# ChargePump.net
KiCad netlist of a schematic drawn in EAGLE
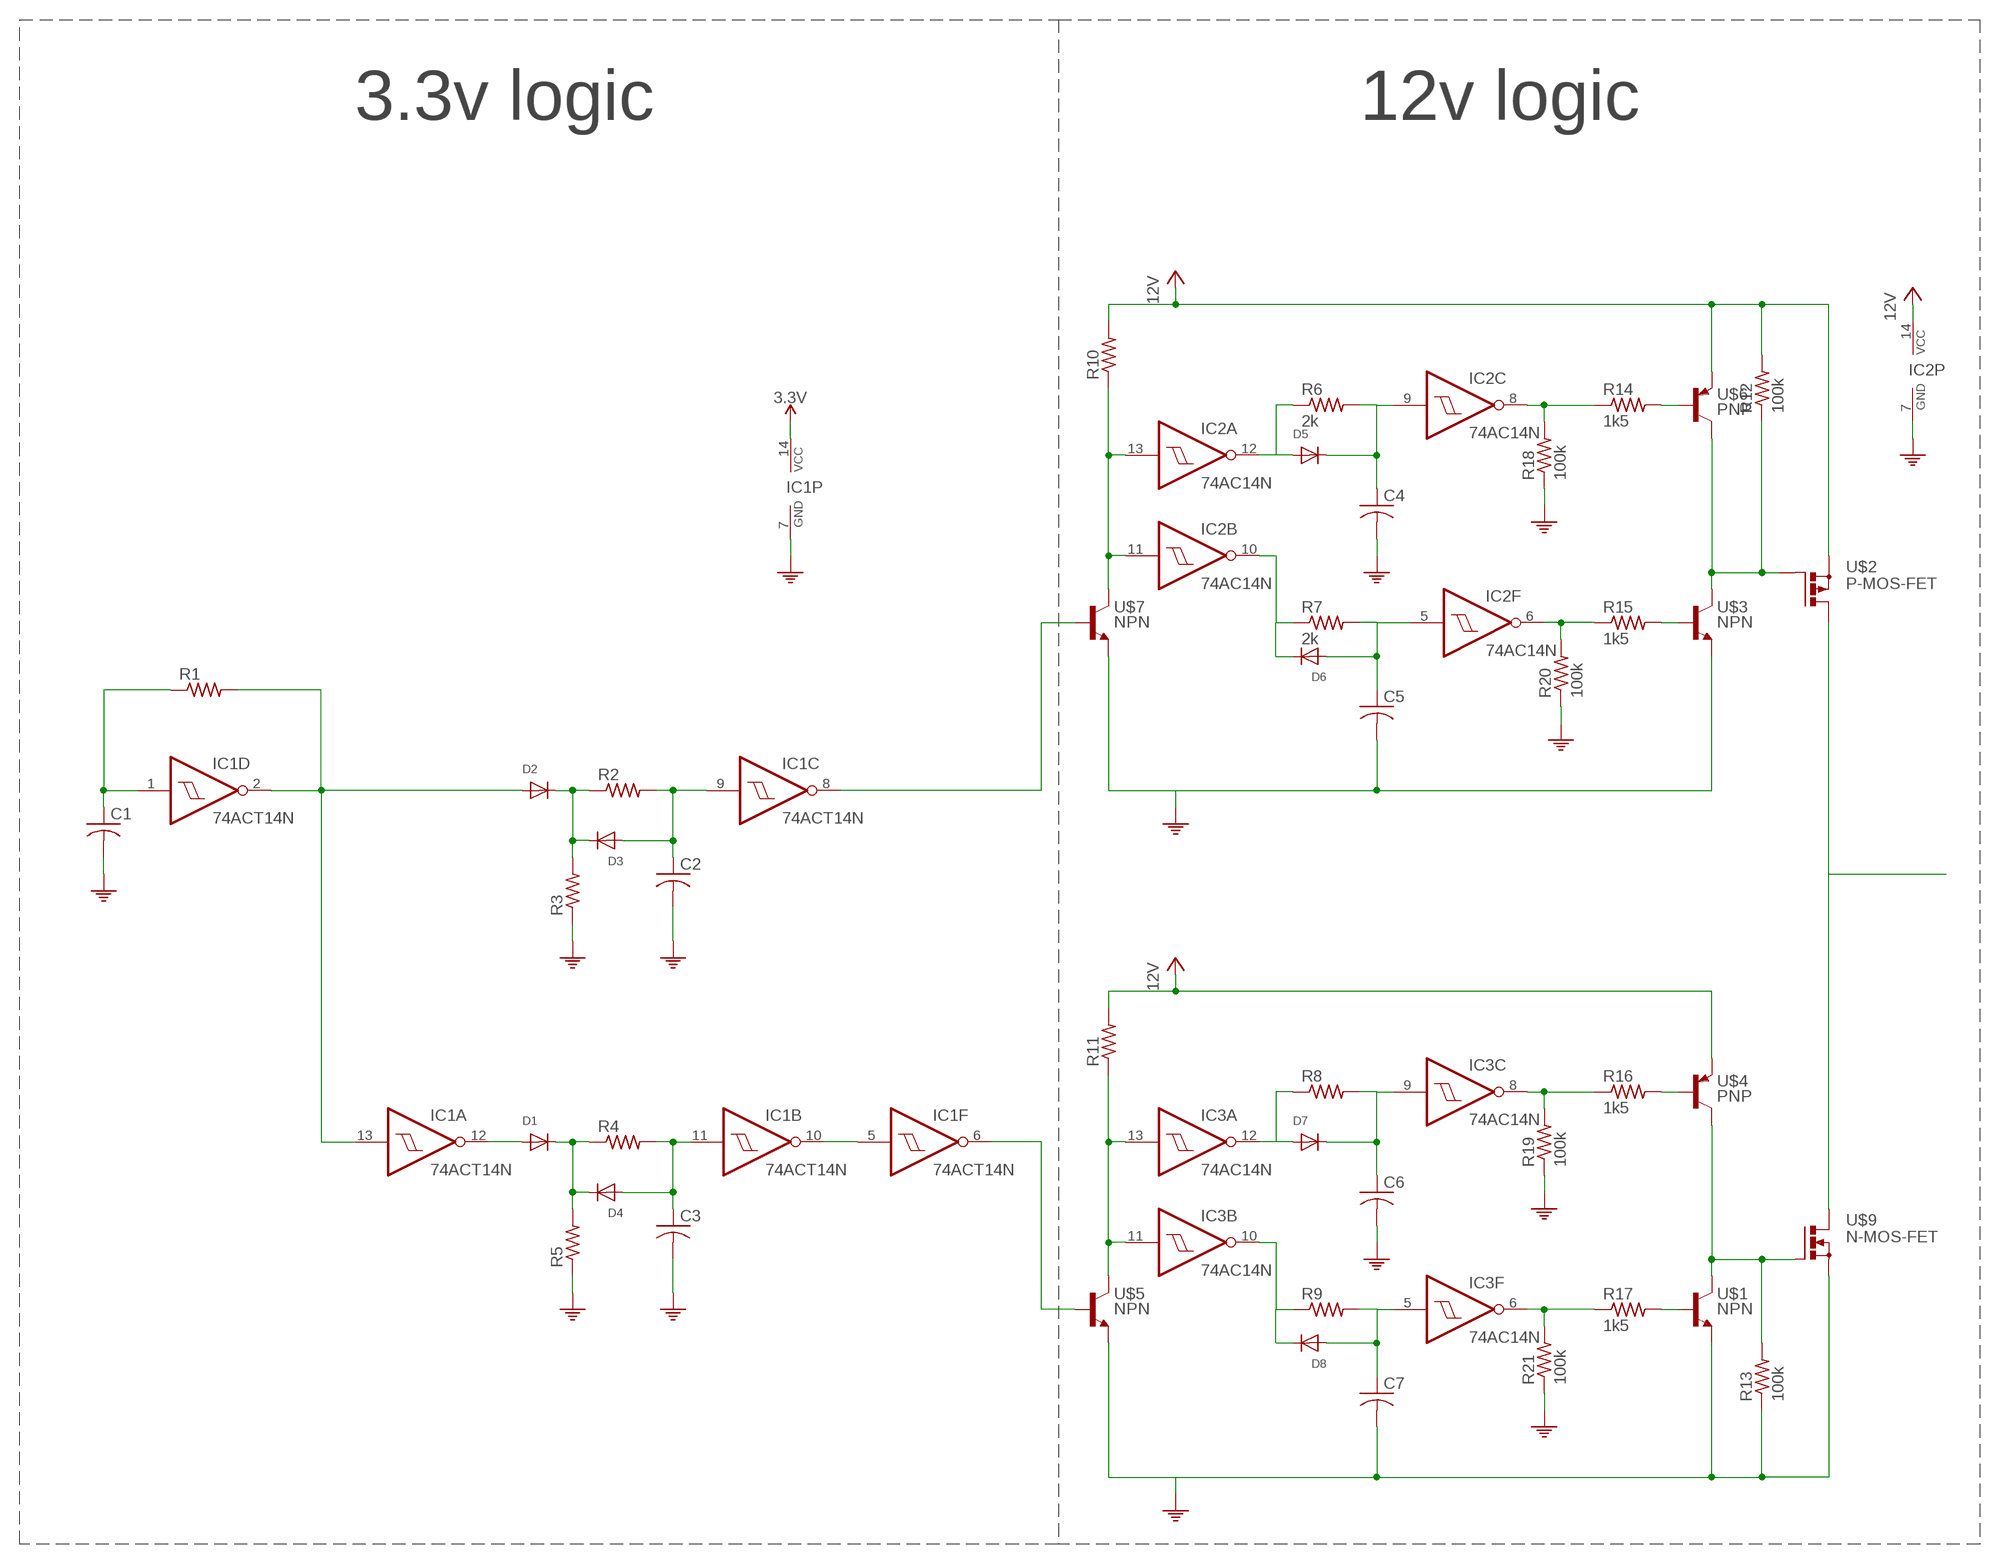
[diagram p0: schematic, sheet 1]

(export (version "E")
  (design (tool "Eeschema 10.0.6"))
  (components
    (comp (ref "C1")
      (value "C-USC0603")
      (footprint "eagle-import:C0603")
      (libsource (lib "eagle-import") (part "C-USC0603"))
    )
    (comp (ref "C2")
      (value "C-USC0603")
      (footprint "eagle-import:C0603")
      (libsource (lib "eagle-import") (part "C-USC0603"))
    )
    (comp (ref "C3")
      (value "C-USC0603")
      (footprint "eagle-import:C0603")
      (libsource (lib "eagle-import") (part "C-USC0603"))
    )
    (comp (ref "C4")
      (value "C-USC0603")
      (footprint "eagle-import:C0603")
      (libsource (lib "eagle-import") (part "C-USC0603"))
    )
    (comp (ref "C5")
      (value "C-USC0603")
      (footprint "eagle-import:C0603")
      (libsource (lib "eagle-import") (part "C-USC0603"))
    )
    (comp (ref "C6")
      (value "C-USC0603")
      (footprint "eagle-import:C0603")
      (libsource (lib "eagle-import") (part "C-USC0603"))
    )
    (comp (ref "C7")
      (value "C-USC0603")
      (footprint "eagle-import:C0603")
      (libsource (lib "eagle-import") (part "C-USC0603"))
    )
    (comp (ref "D1")
      (value "DIODEDO-1N4148")
      (footprint "eagle-import:DO-1N4148")
      (libsource (lib "eagle-import") (part "DIODEDO-1N4148"))
    )
    (comp (ref "D2")
      (value "DIODEDO-1N4148")
      (footprint "eagle-import:DO-1N4148")
      (libsource (lib "eagle-import") (part "DIODEDO-1N4148"))
    )
    (comp (ref "D3")
      (value "DIODEDO-1N4148")
      (footprint "eagle-import:DO-1N4148")
      (libsource (lib "eagle-import") (part "DIODEDO-1N4148"))
    )
    (comp (ref "D4")
      (value "DIODEDO-1N4148")
      (footprint "eagle-import:DO-1N4148")
      (libsource (lib "eagle-import") (part "DIODEDO-1N4148"))
    )
    (comp (ref "D5")
      (value "DIODEDO-1N4148")
      (footprint "eagle-import:DO-1N4148")
      (libsource (lib "eagle-import") (part "DIODEDO-1N4148"))
    )
    (comp (ref "D6")
      (value "DIODEDO-1N4148")
      (footprint "eagle-import:DO-1N4148")
      (libsource (lib "eagle-import") (part "DIODEDO-1N4148"))
    )
    (comp (ref "D7")
      (value "DIODEDO-1N4148")
      (footprint "eagle-import:DO-1N4148")
      (libsource (lib "eagle-import") (part "DIODEDO-1N4148"))
    )
    (comp (ref "D8")
      (value "DIODEDO-1N4148")
      (footprint "eagle-import:DO-1N4148")
      (libsource (lib "eagle-import") (part "DIODEDO-1N4148"))
    )
    (comp (ref "IC1")
      (value "74ACT14N")
      (footprint "eagle-import:DIL14")
      (libsource (lib "eagle-import") (part "7414NACT"))
    )
    (comp (ref "IC2")
      (value "74AC14N")
      (footprint "eagle-import:DIL14")
      (libsource (lib "eagle-import") (part "7414NAC"))
    )
    (comp (ref "IC3")
      (value "74AC14N")
      (footprint "eagle-import:DIL14")
      (libsource (lib "eagle-import") (part "7414NAC"))
    )
    (comp (ref "R1")
      (value "R-US_R0603")
      (footprint "eagle-import:R0603")
      (libsource (lib "eagle-import") (part "R-US_R0603"))
    )
    (comp (ref "R2")
      (value "R-US_R0603")
      (footprint "eagle-import:R0603")
      (libsource (lib "eagle-import") (part "R-US_R0603"))
    )
    (comp (ref "R3")
      (value "R-US_R0603")
      (footprint "eagle-import:R0603")
      (libsource (lib "eagle-import") (part "R-US_R0603"))
    )
    (comp (ref "R4")
      (value "R-US_R0603")
      (footprint "eagle-import:R0603")
      (libsource (lib "eagle-import") (part "R-US_R0603"))
    )
    (comp (ref "R5")
      (value "R-US_R0603")
      (footprint "eagle-import:R0603")
      (libsource (lib "eagle-import") (part "R-US_R0603"))
    )
    (comp (ref "R6")
      (value "2k")
      (footprint "eagle-import:R0603")
      (libsource (lib "eagle-import") (part "R-US_R0603"))
    )
    (comp (ref "R7")
      (value "2k")
      (footprint "eagle-import:R0603")
      (libsource (lib "eagle-import") (part "R-US_R0603"))
    )
    (comp (ref "R8")
      (value "R-US_R0603")
      (footprint "eagle-import:R0603")
      (libsource (lib "eagle-import") (part "R-US_R0603"))
    )
    (comp (ref "R9")
      (value "R-US_R0603")
      (footprint "eagle-import:R0603")
      (libsource (lib "eagle-import") (part "R-US_R0603"))
    )
    (comp (ref "R10")
      (value "R-US_R0603")
      (footprint "eagle-import:R0603")
      (libsource (lib "eagle-import") (part "R-US_R0603"))
    )
    (comp (ref "R11")
      (value "R-US_R0603")
      (footprint "eagle-import:R0603")
      (libsource (lib "eagle-import") (part "R-US_R0603"))
    )
    (comp (ref "R12")
      (value "100k")
      (footprint "eagle-import:R0603")
      (libsource (lib "eagle-import") (part "R-US_R0603"))
    )
    (comp (ref "R13")
      (value "100k")
      (footprint "eagle-import:R0603")
      (libsource (lib "eagle-import") (part "R-US_R0603"))
    )
    (comp (ref "R14")
      (value "1k5")
      (footprint "eagle-import:R0603")
      (libsource (lib "eagle-import") (part "R-US_R0603"))
    )
    (comp (ref "R15")
      (value "1k5")
      (footprint "eagle-import:R0603")
      (libsource (lib "eagle-import") (part "R-US_R0603"))
    )
    (comp (ref "R16")
      (value "1k5")
      (footprint "eagle-import:R0603")
      (libsource (lib "eagle-import") (part "R-US_R0603"))
    )
    (comp (ref "R17")
      (value "1k5")
      (footprint "eagle-import:R0603")
      (libsource (lib "eagle-import") (part "R-US_R0603"))
    )
    (comp (ref "R18")
      (value "100k")
      (footprint "eagle-import:R0603")
      (libsource (lib "eagle-import") (part "R-US_R0603"))
    )
    (comp (ref "R19")
      (value "100k")
      (footprint "eagle-import:R0603")
      (libsource (lib "eagle-import") (part "R-US_R0603"))
    )
    (comp (ref "R20")
      (value "100k")
      (footprint "eagle-import:R0603")
      (libsource (lib "eagle-import") (part "R-US_R0603"))
    )
    (comp (ref "R21")
      (value "100k")
      (footprint "eagle-import:R0603")
      (libsource (lib "eagle-import") (part "R-US_R0603"))
    )
    (comp (ref "U$1")
      (value "NPN")
      (footprint "eagle-import:SOT23")
      (libsource (lib "eagle-import") (part "NPN"))
    )
    (comp (ref "U$2")
      (value "P-MOS-FET")
      (footprint "eagle-import:SOT23")
      (libsource (lib "eagle-import") (part "P-MOS-FET"))
    )
    (comp (ref "U$3")
      (value "NPN")
      (footprint "eagle-import:SOT23")
      (libsource (lib "eagle-import") (part "NPN"))
    )
    (comp (ref "U$4")
      (value "PNP")
      (footprint "eagle-import:SOT23")
      (libsource (lib "eagle-import") (part "PNP"))
    )
    (comp (ref "U$5")
      (value "NPN")
      (footprint "eagle-import:SOT23")
      (libsource (lib "eagle-import") (part "NPN"))
    )
    (comp (ref "U$6")
      (value "PNP")
      (footprint "eagle-import:SOT23")
      (libsource (lib "eagle-import") (part "PNP"))
    )
    (comp (ref "U$7")
      (value "NPN")
      (footprint "eagle-import:SOT23")
      (libsource (lib "eagle-import") (part "NPN"))
    )
    (comp (ref "U$9")
      (value "N-MOS-FET")
      (footprint "eagle-import:SOT23")
      (libsource (lib "eagle-import") (part "N-MOS-FET"))
    )
  )
  (nets
    (net (code "1") (name "3.3V") (class "Default")
      (node (ref "IC1") (pin "14") (pinfunction "VCC_14") (pintype "power_in"))
    )
    (net (code "2") (name "12V") (class "Default")
      (node (ref "IC2") (pin "14") (pinfunction "VCC_14") (pintype "power_in"))
      (node (ref "R10") (pin "2") (pinfunction "2_2") (pintype "passive"))
      (node (ref "R11") (pin "2") (pinfunction "2_2") (pintype "passive"))
      (node (ref "R12") (pin "2") (pinfunction "2_2") (pintype "passive"))
      (node (ref "U$2") (pin "C") (pinfunction "S_C") (pintype "passive"))
      (node (ref "U$4") (pin "E") (pinfunction "E_E") (pintype "passive"))
      (node (ref "U$6") (pin "E") (pinfunction "E_E") (pintype "passive"))
    )
    (net (code "3") (name "GND") (class "Default")
      (node (ref "C1") (pin "2") (pinfunction "2_2") (pintype "passive"))
      (node (ref "C2") (pin "2") (pinfunction "2_2") (pintype "passive"))
      (node (ref "C3") (pin "2") (pinfunction "2_2") (pintype "passive"))
      (node (ref "C4") (pin "2") (pinfunction "2_2") (pintype "passive"))
      (node (ref "C5") (pin "2") (pinfunction "2_2") (pintype "passive"))
      (node (ref "C6") (pin "2") (pinfunction "2_2") (pintype "passive"))
      (node (ref "C7") (pin "2") (pinfunction "2_2") (pintype "passive"))
      (node (ref "IC1") (pin "7") (pinfunction "GND_7") (pintype "power_in"))
      (node (ref "IC2") (pin "7") (pinfunction "GND_7") (pintype "power_in"))
      (node (ref "R13") (pin "1") (pinfunction "1_1") (pintype "passive"))
      (node (ref "R18") (pin "1") (pinfunction "1_1") (pintype "passive"))
      (node (ref "R19") (pin "1") (pinfunction "1_1") (pintype "passive"))
      (node (ref "R20") (pin "1") (pinfunction "1_1") (pintype "passive"))
      (node (ref "R21") (pin "1") (pinfunction "1_1") (pintype "passive"))
      (node (ref "R3") (pin "1") (pinfunction "1_1") (pintype "passive"))
      (node (ref "R5") (pin "1") (pinfunction "1_1") (pintype "passive"))
      (node (ref "U$1") (pin "E") (pinfunction "E_E") (pintype "passive"))
      (node (ref "U$3") (pin "E") (pinfunction "E_E") (pintype "passive"))
      (node (ref "U$5") (pin "E") (pinfunction "E_E") (pintype "passive"))
      (node (ref "U$7") (pin "E") (pinfunction "E_E") (pintype "passive"))
      (node (ref "U$9") (pin "E") (pinfunction "S_E") (pintype "passive"))
    )
    (net (code "4") (name "Net-(D1-PadC)") (class "Default")
      (node (ref "D1") (pin "C") (pinfunction "C_C") (pintype "passive"))
      (node (ref "D4") (pin "C") (pinfunction "C_C") (pintype "passive"))
      (node (ref "R4") (pin "1") (pinfunction "1_1") (pintype "passive"))
      (node (ref "R5") (pin "2") (pinfunction "2_2") (pintype "passive"))
    )
    (net (code "5") (name "Net-(D2-PadC)") (class "Default")
      (node (ref "D2") (pin "C") (pinfunction "C_C") (pintype "passive"))
      (node (ref "D3") (pin "C") (pinfunction "C_C") (pintype "passive"))
      (node (ref "R2") (pin "1") (pinfunction "1_1") (pintype "passive"))
      (node (ref "R3") (pin "2") (pinfunction "2_2") (pintype "passive"))
    )
    (net (code "6") (name "Net-(IC1A-I)") (class "Default")
      (node (ref "D2") (pin "A") (pinfunction "A_A") (pintype "passive"))
      (node (ref "IC1") (pin "13") (pinfunction "I_13") (pintype "input"))
      (node (ref "IC1") (pin "2") (pinfunction "O_2") (pintype "output"))
      (node (ref "R1") (pin "2") (pinfunction "2_2") (pintype "passive"))
    )
    (net (code "7") (name "Net-(IC1A-O)") (class "Default")
      (node (ref "D1") (pin "A") (pinfunction "A_A") (pintype "passive"))
      (node (ref "IC1") (pin "12") (pinfunction "O_12") (pintype "output"))
    )
    (net (code "8") (name "Net-(IC1B-I)") (class "Default")
      (node (ref "C3") (pin "1") (pinfunction "1_1") (pintype "passive"))
      (node (ref "D4") (pin "A") (pinfunction "A_A") (pintype "passive"))
      (node (ref "IC1") (pin "11") (pinfunction "I_11") (pintype "input"))
      (node (ref "R4") (pin "2") (pinfunction "2_2") (pintype "passive"))
    )
    (net (code "9") (name "Net-(IC1B-O)") (class "Default")
      (node (ref "IC1") (pin "10") (pinfunction "O_10") (pintype "output"))
      (node (ref "IC1") (pin "5") (pinfunction "I_5") (pintype "input"))
    )
    (net (code "10") (name "Net-(IC1C-I)") (class "Default")
      (node (ref "C2") (pin "1") (pinfunction "1_1") (pintype "passive"))
      (node (ref "D3") (pin "A") (pinfunction "A_A") (pintype "passive"))
      (node (ref "IC1") (pin "9") (pinfunction "I_9") (pintype "input"))
      (node (ref "R2") (pin "2") (pinfunction "2_2") (pintype "passive"))
    )
    (net (code "11") (name "Net-(IC1C-O)") (class "Default")
      (node (ref "IC1") (pin "8") (pinfunction "O_8") (pintype "output"))
      (node (ref "U$7") (pin "B") (pinfunction "B_B") (pintype "passive"))
    )
    (net (code "12") (name "Net-(IC1D-I)") (class "Default")
      (node (ref "C1") (pin "1") (pinfunction "1_1") (pintype "passive"))
      (node (ref "IC1") (pin "1") (pinfunction "I_1") (pintype "input"))
      (node (ref "R1") (pin "1") (pinfunction "1_1") (pintype "passive"))
    )
    (net (code "13") (name "Net-(IC1F-O)") (class "Default")
      (node (ref "IC1") (pin "6") (pinfunction "O_6") (pintype "output"))
      (node (ref "U$5") (pin "B") (pinfunction "B_B") (pintype "passive"))
    )
    (net (code "14") (name "Net-(IC2A-I)") (class "Default")
      (node (ref "IC2") (pin "11") (pinfunction "I_11") (pintype "input"))
      (node (ref "IC2") (pin "13") (pinfunction "I_13") (pintype "input"))
      (node (ref "R10") (pin "1") (pinfunction "1_1") (pintype "passive"))
      (node (ref "U$7") (pin "C") (pinfunction "C_C") (pintype "passive"))
    )
    (net (code "15") (name "Net-(IC2A-O)") (class "Default")
      (node (ref "D5") (pin "A") (pinfunction "A_A") (pintype "passive"))
      (node (ref "IC2") (pin "12") (pinfunction "O_12") (pintype "output"))
      (node (ref "R6") (pin "1") (pinfunction "1_1") (pintype "passive"))
    )
    (net (code "16") (name "Net-(IC2B-O)") (class "Default")
      (node (ref "D6") (pin "C") (pinfunction "C_C") (pintype "passive"))
      (node (ref "IC2") (pin "10") (pinfunction "O_10") (pintype "output"))
      (node (ref "R7") (pin "1") (pinfunction "1_1") (pintype "passive"))
    )
    (net (code "17") (name "Net-(IC2C-I)") (class "Default")
      (node (ref "C4") (pin "1") (pinfunction "1_1") (pintype "passive"))
      (node (ref "D5") (pin "C") (pinfunction "C_C") (pintype "passive"))
      (node (ref "IC2") (pin "9") (pinfunction "I_9") (pintype "input"))
      (node (ref "R6") (pin "2") (pinfunction "2_2") (pintype "passive"))
    )
    (net (code "18") (name "Net-(IC2C-O)") (class "Default")
      (node (ref "IC2") (pin "8") (pinfunction "O_8") (pintype "output"))
      (node (ref "R14") (pin "1") (pinfunction "1_1") (pintype "passive"))
      (node (ref "R18") (pin "2") (pinfunction "2_2") (pintype "passive"))
    )
    (net (code "19") (name "Net-(IC2F-I)") (class "Default")
      (node (ref "C5") (pin "1") (pinfunction "1_1") (pintype "passive"))
      (node (ref "D6") (pin "A") (pinfunction "A_A") (pintype "passive"))
      (node (ref "IC2") (pin "5") (pinfunction "I_5") (pintype "input"))
      (node (ref "R7") (pin "2") (pinfunction "2_2") (pintype "passive"))
    )
    (net (code "20") (name "Net-(IC2F-O)") (class "Default")
      (node (ref "IC2") (pin "6") (pinfunction "O_6") (pintype "output"))
      (node (ref "R15") (pin "1") (pinfunction "1_1") (pintype "passive"))
      (node (ref "R20") (pin "2") (pinfunction "2_2") (pintype "passive"))
    )
    (net (code "21") (name "Net-(IC3A-I)") (class "Default")
      (node (ref "IC3") (pin "11") (pinfunction "I_11") (pintype "input"))
      (node (ref "IC3") (pin "13") (pinfunction "I_13") (pintype "input"))
      (node (ref "R11") (pin "1") (pinfunction "1_1") (pintype "passive"))
      (node (ref "U$5") (pin "C") (pinfunction "C_C") (pintype "passive"))
    )
    (net (code "22") (name "Net-(IC3A-O)") (class "Default")
      (node (ref "D7") (pin "A") (pinfunction "A_A") (pintype "passive"))
      (node (ref "IC3") (pin "12") (pinfunction "O_12") (pintype "output"))
      (node (ref "R8") (pin "1") (pinfunction "1_1") (pintype "passive"))
    )
    (net (code "23") (name "Net-(IC3B-O)") (class "Default")
      (node (ref "D8") (pin "C") (pinfunction "C_C") (pintype "passive"))
      (node (ref "IC3") (pin "10") (pinfunction "O_10") (pintype "output"))
      (node (ref "R9") (pin "1") (pinfunction "1_1") (pintype "passive"))
    )
    (net (code "24") (name "Net-(IC3C-I)") (class "Default")
      (node (ref "C6") (pin "1") (pinfunction "1_1") (pintype "passive"))
      (node (ref "D7") (pin "C") (pinfunction "C_C") (pintype "passive"))
      (node (ref "IC3") (pin "9") (pinfunction "I_9") (pintype "input"))
      (node (ref "R8") (pin "2") (pinfunction "2_2") (pintype "passive"))
    )
    (net (code "25") (name "Net-(IC3C-O)") (class "Default")
      (node (ref "IC3") (pin "8") (pinfunction "O_8") (pintype "output"))
      (node (ref "R16") (pin "1") (pinfunction "1_1") (pintype "passive"))
      (node (ref "R19") (pin "2") (pinfunction "2_2") (pintype "passive"))
    )
    (net (code "26") (name "Net-(IC3F-I)") (class "Default")
      (node (ref "C7") (pin "1") (pinfunction "1_1") (pintype "passive"))
      (node (ref "D8") (pin "A") (pinfunction "A_A") (pintype "passive"))
      (node (ref "IC3") (pin "5") (pinfunction "I_5") (pintype "input"))
      (node (ref "R9") (pin "2") (pinfunction "2_2") (pintype "passive"))
    )
    (net (code "27") (name "Net-(IC3F-O)") (class "Default")
      (node (ref "IC3") (pin "6") (pinfunction "O_6") (pintype "output"))
      (node (ref "R17") (pin "1") (pinfunction "1_1") (pintype "passive"))
      (node (ref "R21") (pin "2") (pinfunction "2_2") (pintype "passive"))
    )
    (net (code "28") (name "Net-(R14-Pad2)") (class "Default")
      (node (ref "R14") (pin "2") (pinfunction "2_2") (pintype "passive"))
      (node (ref "U$6") (pin "B") (pinfunction "B_B") (pintype "passive"))
    )
    (net (code "29") (name "Net-(R15-Pad2)") (class "Default")
      (node (ref "R15") (pin "2") (pinfunction "2_2") (pintype "passive"))
      (node (ref "U$3") (pin "B") (pinfunction "B_B") (pintype "passive"))
    )
    (net (code "30") (name "Net-(R16-Pad2)") (class "Default")
      (node (ref "R16") (pin "2") (pinfunction "2_2") (pintype "passive"))
      (node (ref "U$4") (pin "B") (pinfunction "B_B") (pintype "passive"))
    )
    (net (code "31") (name "Net-(R17-Pad2)") (class "Default")
      (node (ref "R17") (pin "2") (pinfunction "2_2") (pintype "passive"))
      (node (ref "U$1") (pin "B") (pinfunction "B_B") (pintype "passive"))
    )
    (net (code "32") (name "Net-(U$2-D)") (class "Default")
      (node (ref "U$2") (pin "E") (pinfunction "D_E") (pintype "passive"))
      (node (ref "U$9") (pin "C") (pinfunction "D_C") (pintype "passive"))
    )
    (net (code "33") (name "Net-(U$2-G)") (class "Default")
      (node (ref "R12") (pin "1") (pinfunction "1_1") (pintype "passive"))
      (node (ref "U$2") (pin "B") (pinfunction "G_B") (pintype "passive"))
      (node (ref "U$3") (pin "C") (pinfunction "C_C") (pintype "passive"))
      (node (ref "U$6") (pin "C") (pinfunction "C_C") (pintype "passive"))
    )
    (net (code "34") (name "Net-(U$9-G)") (class "Default")
      (node (ref "R13") (pin "2") (pinfunction "2_2") (pintype "passive"))
      (node (ref "U$1") (pin "C") (pinfunction "C_C") (pintype "passive"))
      (node (ref "U$4") (pin "C") (pinfunction "C_C") (pintype "passive"))
      (node (ref "U$9") (pin "B") (pinfunction "G_B") (pintype "passive"))
    )
  )
)
